# MB1297_STLINK_V2-1.net
KiCad netlist of a schematic drawn in Altium Designer
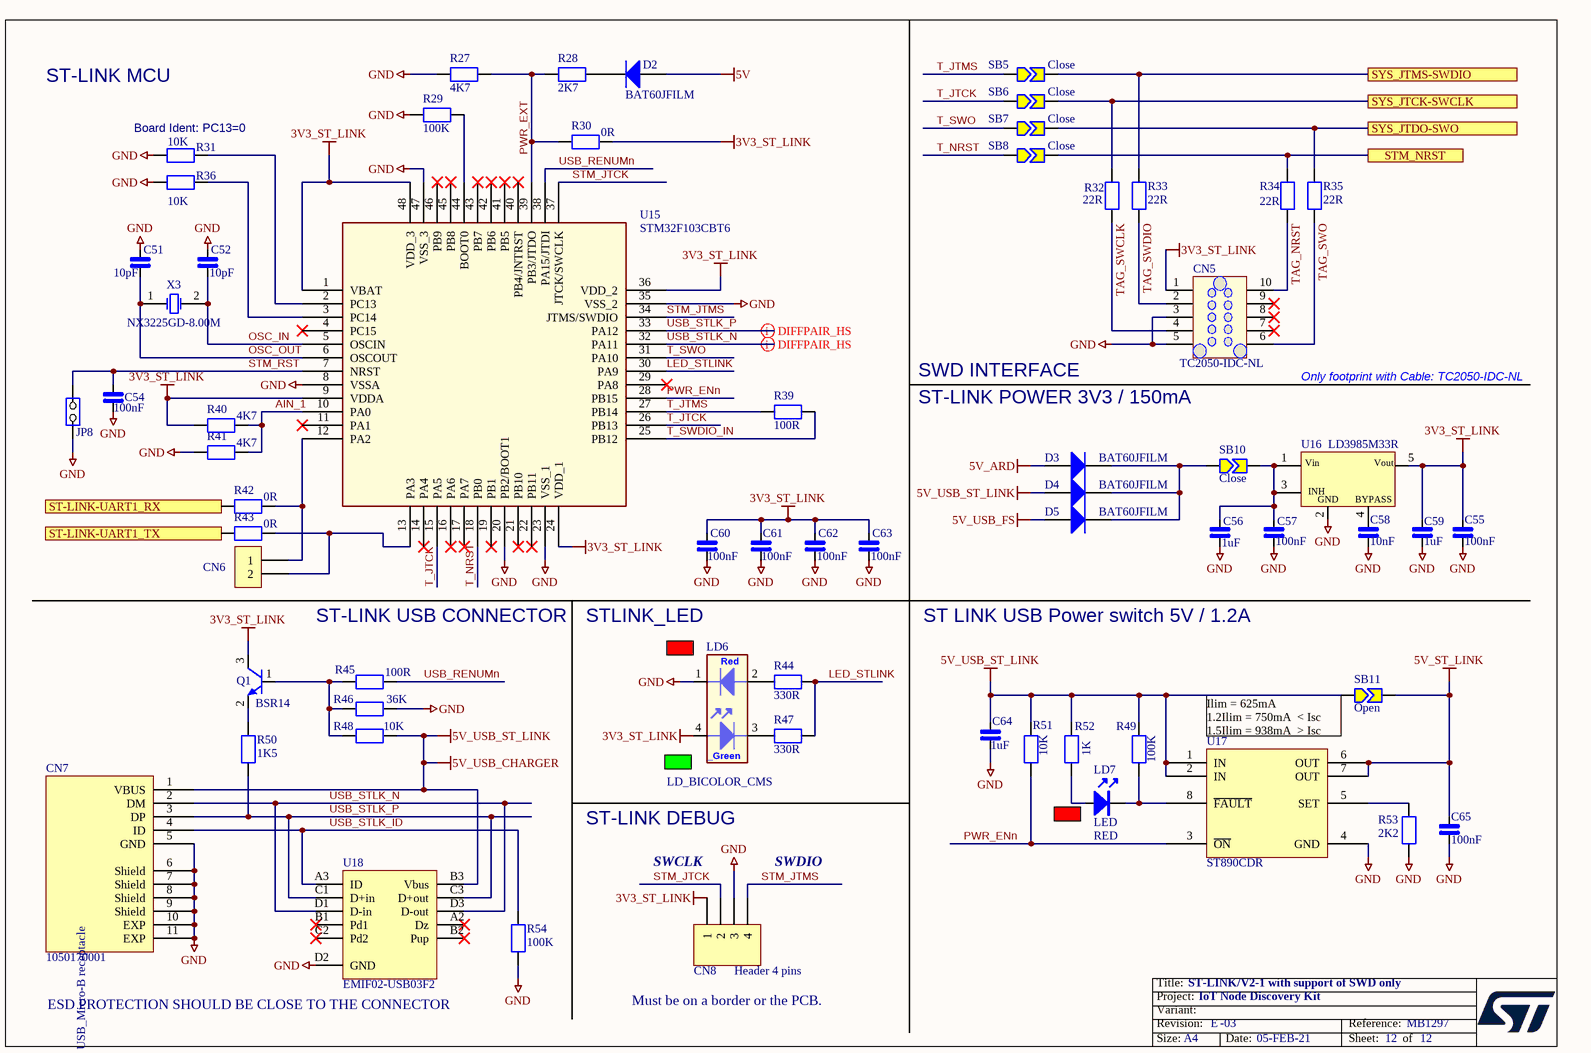
[diagram p0: MB1297_STLINK_V2-1.SCHDOC]

(export (version "E")
  (design (tool "Eeschema 10.0.6"))
  (components
    (comp (ref "C51")
      (value "10pF")
      (footprint "0402")
      (description "Capacitor_not polarized")
      (libsource (lib "ST_Lib3D") (part "CAP_NPOL"))
    )
    (comp (ref "C52")
      (value "10pF")
      (footprint "0402")
      (description "Capacitor_not polarized")
      (libsource (lib "ST_Lib3D") (part "CAP_NPOL"))
    )
    (comp (ref "C54")
      (value "100nF")
      (footprint "0402")
      (description "Capacitor_not polarized")
      (libsource (lib "ST_Lib3D") (part "CAP_NPOL"))
    )
    (comp (ref "C55")
      (value "100nF")
      (footprint "0402")
      (description "Capacitor_not polarized")
      (libsource (lib "ST_Lib3D") (part "CAP_NPOL"))
    )
    (comp (ref "C56")
      (value "1uF")
      (footprint "0402")
      (description "Capacitor_not polarized")
      (libsource (lib "ST_Lib3D") (part "CAP_NPOL"))
    )
    (comp (ref "C57")
      (value "100nF")
      (footprint "0402")
      (description "Capacitor_not polarized")
      (libsource (lib "ST_Lib3D") (part "CAP_NPOL"))
    )
    (comp (ref "C58")
      (value "10nF")
      (footprint "0402")
      (description "Capacitor_not polarized")
      (libsource (lib "ST_Lib3D") (part "CAP_NPOL"))
    )
    (comp (ref "C59")
      (value "1uF")
      (footprint "0402")
      (description "Capacitor_not polarized")
      (libsource (lib "ST_Lib3D") (part "CAP_NPOL"))
    )
    (comp (ref "C60")
      (value "100nF")
      (footprint "0402")
      (description "Capacitor_not polarized")
      (libsource (lib "ST_Lib3D") (part "CAP_NPOL"))
    )
    (comp (ref "C61")
      (value "100nF")
      (footprint "0402")
      (description "Capacitor_not polarized")
      (libsource (lib "ST_Lib3D") (part "CAP_NPOL"))
    )
    (comp (ref "C62")
      (value "100nF")
      (footprint "0402")
      (description "Capacitor_not polarized")
      (libsource (lib "ST_Lib3D") (part "CAP_NPOL"))
    )
    (comp (ref "C63")
      (value "100nF")
      (footprint "0402")
      (description "Capacitor_not polarized")
      (libsource (lib "ST_Lib3D") (part "CAP_NPOL"))
    )
    (comp (ref "C64")
      (value "1uF")
      (footprint "0402")
      (description "Capacitor_not polarized")
      (libsource (lib "ST_Lib3D") (part "CAP_NPOL"))
    )
    (comp (ref "C65")
      (value "100nF")
      (footprint "0402")
      (description "Capacitor_not polarized")
      (libsource (lib "ST_Lib3D") (part "CAP_NPOL"))
    )
    (comp (ref "CN5")
      (value "TC2050-IDC-NL")
      (footprint "CON_TAG-C_TC2050-IDC-NL")
      (description "Tag_Connector Header, 10-Pin, Dual row No legs")
      (libsource (lib "MCD_TEMP_PCH") (part "Tag-10-C"))
    )
    (comp (ref "CN6")
      (value "header 2 pins 2.54mm")
      (footprint "CON_SAMTEC_TSW-102-07-G-S")
      (description "Header 2 pins")
      (libsource (lib "MCD_TEMP_PCH") (part "Header 2 pins"))
    )
    (comp (ref "CN7")
      (value "1050170001")
      (footprint "CON_USBMICROB_MOLEX_105017-0001_H2P90")
      (description "USB-MICRO-B, 1050170001, SMT, MOLEX")
      (libsource (lib "MCD_TEMP_PCH") (part "1050170001"))
    )
    (comp (ref "CN8")
      (value "Header 4 pins")
      (footprint "CON_SAMTEC_TSW-104-07-G-S")
      (description "Header, 4-Pin")
      (libsource (lib "MCD_TEMP_PCH") (part "Header 4"))
    )
    (comp (ref "D2")
      (value "BAT60JFILM")
      (footprint "DIO_SOD323")
      (libsource (lib "MCD_TEMP_PCH") (part "BAT60JFILM"))
    )
    (comp (ref "D3")
      (value "BAT60JFILM")
      (footprint "DIO_SOD323")
      (libsource (lib "MCD_TEMP_PCH") (part "BAT60JFILM"))
    )
    (comp (ref "D4")
      (value "BAT60JFILM")
      (footprint "DIO_SOD323")
      (libsource (lib "MCD_TEMP_PCH") (part "BAT60JFILM"))
    )
    (comp (ref "D5")
      (value "BAT60JFILM")
      (footprint "DIO_SOD323")
      (libsource (lib "MCD_TEMP_PCH") (part "BAT60JFILM"))
    )
    (comp (ref "JP8")
      (value "Jumper_2.54mm")
      (footprint "CON_SAMTEC_TSW-102-07-G-S")
      (description "Connector jumper 1 position")
      (libsource (lib "MCD_TEMP_PCH") (part "TSW-102-07-x-S"))
    )
    (comp (ref "LD6")
      (value "LD_BICOLOR_CMS")
      (footprint "LED_BI-GR_HSMF-A201-A00J1")
      (description "Bicolor Led")
      (libsource (lib "MCD_TEMP_PCH") (part "LD_BICOLOR_CMS"))
    )
    (comp (ref "LD7")
      (value "LED")
      (footprint "0603_LED_RED")
      (description "Light-Emitting Diode")
      (fields (field (name "COLOR") "RED"))
      (libsource (lib "ST_Lib3D") (part "LED"))
    )
    (comp (ref "Q1")
      (value "BSR14")
      (footprint "ST_Lib3D:SOT23-3")
      (description "BSR14 NPN switching transistor SOT23 (Marking U8)")
      (libsource (lib "ST_Lib3D") (part "BSR14"))
    )
    (comp (ref "R27")
      (value "4K7")
      (footprint "0402")
      (description "Resistor")
      (libsource (lib "Lib3D_Altium10_Schlib") (part "RES"))
    )
    (comp (ref "R28")
      (value "2K7")
      (footprint "0402")
      (description "Resistor")
      (libsource (lib "Lib3D_Altium10_Schlib") (part "RES"))
    )
    (comp (ref "R29")
      (value "100K")
      (footprint "0402")
      (description "Resistor")
      (libsource (lib "Lib3D_Altium10_Schlib") (part "RES"))
    )
    (comp (ref "R30")
      (value "0R")
      (footprint "0402_RES")
      (description "Resistor")
      (libsource (lib "Lib3D_Altium10_Schlib") (part "RES"))
    )
    (comp (ref "R31")
      (value "10K")
      (footprint "0402")
      (description "Resistor")
      (libsource (lib "Lib3D_Altium10_Schlib") (part "RES"))
    )
    (comp (ref "R32")
      (value "22R")
      (footprint "0402")
      (description "Resistor")
      (libsource (lib "Lib3D_Altium10_Schlib") (part "RES"))
    )
    (comp (ref "R33")
      (value "22R")
      (footprint "0402")
      (description "Resistor")
      (libsource (lib "Lib3D_Altium10_Schlib") (part "RES"))
    )
    (comp (ref "R34")
      (value "22R")
      (footprint "0402")
      (description "Resistor")
      (libsource (lib "Lib3D_Altium10_Schlib") (part "RES"))
    )
    (comp (ref "R35")
      (value "22R")
      (footprint "0402")
      (description "Resistor")
      (libsource (lib "Lib3D_Altium10_Schlib") (part "RES"))
    )
    (comp (ref "R36")
      (value "10K")
      (footprint "0402")
      (description "Resistor")
      (libsource (lib "Lib3D_Altium10_Schlib") (part "RES"))
    )
    (comp (ref "R39")
      (value "100R")
      (footprint "0402")
      (description "Resistor")
      (libsource (lib "Lib3D_Altium10_Schlib") (part "RES"))
    )
    (comp (ref "R40")
      (value "4K7")
      (footprint "0402")
      (description "Resistor")
      (libsource (lib "Lib3D_Altium10_Schlib") (part "RES"))
    )
    (comp (ref "R41")
      (value "4K7")
      (footprint "0402")
      (description "Resistor")
      (libsource (lib "Lib3D_Altium10_Schlib") (part "RES"))
    )
    (comp (ref "R42")
      (value "0R")
      (footprint "0402_RES")
      (description "Resistor")
      (libsource (lib "Lib3D_Altium10_Schlib") (part "RES"))
    )
    (comp (ref "R43")
      (value "0R")
      (footprint "0402_RES")
      (description "Resistor")
      (libsource (lib "Lib3D_Altium10_Schlib") (part "RES"))
    )
    (comp (ref "R44")
      (value "330R")
      (footprint "0402")
      (description "Resistor")
      (libsource (lib "Lib3D_Altium10_Schlib") (part "RES"))
    )
    (comp (ref "R45")
      (value "100R")
      (footprint "0402")
      (description "Resistor")
      (libsource (lib "Lib3D_Altium10_Schlib") (part "RES"))
    )
    (comp (ref "R46")
      (value "36K")
      (footprint "0402")
      (description "Resistor")
      (libsource (lib "Lib3D_Altium10_Schlib") (part "RES"))
    )
    (comp (ref "R47")
      (value "330R")
      (footprint "0402")
      (description "Resistor")
      (libsource (lib "Lib3D_Altium10_Schlib") (part "RES"))
    )
    (comp (ref "R48")
      (value "10K")
      (footprint "0402")
      (description "Resistor")
      (libsource (lib "Lib3D_Altium10_Schlib") (part "RES"))
    )
    (comp (ref "R49")
      (value "100K")
      (footprint "0402_RES")
      (description "Resistor")
      (libsource (lib "Lib3D_Altium10_Schlib") (part "RES"))
    )
    (comp (ref "R50")
      (value "1K5")
      (footprint "0402_RES")
      (description "Resistor")
      (libsource (lib "Lib3D_Altium10_Schlib") (part "RES"))
    )
    (comp (ref "R51")
      (value "10K")
      (footprint "0402")
      (description "Resistor")
      (libsource (lib "Lib3D_Altium10_Schlib") (part "RES"))
    )
    (comp (ref "R52")
      (value "1K")
      (footprint "0402")
      (description "Resistor")
      (libsource (lib "Lib3D_Altium10_Schlib") (part "RES"))
    )
    (comp (ref "R53")
      (value "2K2")
      (footprint "0402")
      (description "Resistor")
      (libsource (lib "Lib3D_Altium10_Schlib") (part "RES"))
    )
    (comp (ref "R54")
      (value "100K")
      (footprint "0402")
      (description "Resistor")
      (libsource (lib "Lib3D_Altium10_Schlib") (part "RES"))
    )
    (comp (ref "SB5")
      (value "Close")
      (footprint "SB")
      (description "Solder Jumper")
      (fields (field (name "PUBLISHER") "Altium Limited"))
      (libsource (lib "Lib3D_Altium10_Schlib") (part "Strap2"))
    )
    (comp (ref "SB6")
      (value "Close")
      (footprint "SB")
      (description "Solder Jumper")
      (fields (field (name "PUBLISHER") "Altium Limited"))
      (libsource (lib "Lib3D_Altium10_Schlib") (part "Strap2"))
    )
    (comp (ref "SB7")
      (value "Close")
      (footprint "SB")
      (description "Solder Jumper")
      (fields (field (name "PUBLISHER") "Altium Limited"))
      (libsource (lib "Lib3D_Altium10_Schlib") (part "Strap2"))
    )
    (comp (ref "SB8")
      (value "Close")
      (footprint "SB")
      (description "Solder Jumper")
      (fields (field (name "PUBLISHER") "Altium Limited"))
      (libsource (lib "Lib3D_Altium10_Schlib") (part "Strap2"))
    )
    (comp (ref "SB10")
      (value "Close")
      (footprint "SB")
      (description "Solder Jumper")
      (fields (field (name "PUBLISHER") "Altium Limited"))
      (libsource (lib "Lib3D_Altium10_Schlib") (part "Strap2"))
    )
    (comp (ref "SB11")
      (value "Open")
      (footprint "SB")
      (description "Solder Jumper")
      (fields (field (name "PUBLISHER") "Altium Limited"))
      (libsource (lib "Lib3D_Altium10_Schlib") (part "Strap2"))
    )
    (comp (ref "U15")
      (value "STM32F103CBT6")
      (footprint "ICC_LQFP48_7X7_P050")
      (description "Medium-density performance line ARM-based 32-bit MCU with 128KB Flash")
      (libsource (lib "MCD_TEMP_PCH") (part "STM32F103CBT6"))
    )
    (comp (ref "U16")
      (value "LD3985M33R")
      (footprint "REG_SOT23-5L")
      (description "Ultra low drop-low noise BiCMOS voltage, regulators low ESR capacitors compatible")
      (libsource (lib "MCD_TEMP_PCH") (part "LD3985M33R"))
    )
    (comp (ref "U17")
      (value "ST890CDR")
      (footprint "ICC_SO8_5X4_P127")
      (description "1.2 A current limited high-side power switch with thermal shutdown")
      (libsource (lib "MCD_TEMP_PCH") (part "ST890CDR"))
    )
    (comp (ref "U18")
      (value "EMIF02-USB03F2")
      (footprint "ESD_FLIP-CHIP-BGA11_1P44X1P94_P050")
      (description "2-line IPAD, EMI filter including ESD protection")
      (libsource (lib "MCD_TEMP_PCH") (part "EMIF02-USB03F2"))
    )
    (comp (ref "X3")
      (value "NX3225GD-8.00M")
      (footprint "CRY_NX3225GD_2P")
      (description "Crystal 8Mhz, 8pF, -+50PPM, SMD")
      (libsource (lib "MCD_TEMP_PCH") (part "XTAL_8M_NX3225GD"))
    )
  )
  (nets
    (net (code "1") (name "/AIN_1") (class "Default")
      (node (ref "R40") (pin "1") (pinfunction "1_1") (pintype "passive"))
      (node (ref "R41") (pin "1") (pinfunction "1_1") (pintype "passive"))
      (node (ref "U15") (pin "10") (pinfunction "PA0_10") (pintype "passive"))
    )
    (net (code "2") (name "/LED_STLINK") (class "Default")
      (node (ref "R44") (pin "1") (pinfunction "1_1") (pintype "passive"))
      (node (ref "R47") (pin "1") (pinfunction "1_1") (pintype "passive"))
      (node (ref "U15") (pin "30") (pinfunction "PA9_30") (pintype "passive"))
    )
    (net (code "3") (name "/OSC_IN") (class "Default")
      (node (ref "C52") (pin "2") (pinfunction "2_2") (pintype "passive"))
      (node (ref "U15") (pin "5") (pinfunction "OSCIN_5") (pintype "passive"))
      (node (ref "X3") (pin "2") (pinfunction "OSC2_2") (pintype "passive"))
    )
    (net (code "4") (name "/OSC_OUT") (class "Default")
      (node (ref "C51") (pin "2") (pinfunction "2_2") (pintype "passive"))
      (node (ref "U15") (pin "6") (pinfunction "OSCOUT_6") (pintype "passive"))
      (node (ref "X3") (pin "1") (pinfunction "OSC1_1") (pintype "passive"))
    )
    (net (code "5") (name "/PWR_ENn") (class "Default")
      (node (ref "R51") (pin "1") (pinfunction "1_1") (pintype "passive"))
      (node (ref "U15") (pin "28") (pinfunction "PB15_28") (pintype "passive"))
      (node (ref "U17") (pin "3") (pinfunction "~{ON}_3") (pintype "passive"))
    )
    (net (code "6") (name "/PWR_EXT") (class "Default")
      (node (ref "R27") (pin "1") (pinfunction "1_1") (pintype "passive"))
      (node (ref "R28") (pin "2") (pinfunction "2_2") (pintype "passive"))
      (node (ref "R30") (pin "2") (pinfunction "2_2") (pintype "passive"))
      (node (ref "U15") (pin "39") (pinfunction "PB3/JTDO_39") (pintype "passive"))
    )
    (net (code "7") (name "/ST-LINK-UART1_RX") (class "Default")
      (node (ref "R42") (pin "2") (pinfunction "2_2") (pintype "passive"))
    )
    (net (code "8") (name "/ST-LINK-UART1_TX") (class "Default")
      (node (ref "R43") (pin "2") (pinfunction "2_2") (pintype "passive"))
    )
    (net (code "9") (name "/STM_JTCK") (class "Default")
      (node (ref "CN8") (pin "2") (pinfunction "2_2") (pintype "passive"))
      (node (ref "U15") (pin "37") (pinfunction "JTCK/SWCLK_37") (pintype "passive"))
    )
    (net (code "10") (name "/STM_JTMS") (class "Default")
      (node (ref "CN8") (pin "4") (pinfunction "4_4") (pintype "passive"))
      (node (ref "U15") (pin "34") (pinfunction "JTMS/SWDIO_34") (pintype "passive"))
    )
    (net (code "11") (name "/STM_NRST") (class "Default")
      (node (ref "R34") (pin "2") (pinfunction "2_2") (pintype "passive"))
      (node (ref "SB8") (pin "1") (pinfunction "1_1") (pintype "passive"))
    )
    (net (code "12") (name "/STM_RST") (class "Default")
      (node (ref "C54") (pin "1") (pinfunction "1_1") (pintype "passive"))
      (node (ref "JP8") (pin "2") (pinfunction "NO_2") (pintype "passive"))
      (node (ref "U15") (pin "7") (pinfunction "NRST_7") (pintype "passive"))
    )
    (net (code "13") (name "/SYS_JTCK-SWCLK") (class "Default")
      (node (ref "R32") (pin "2") (pinfunction "2_2") (pintype "passive"))
      (node (ref "SB6") (pin "1") (pinfunction "1_1") (pintype "passive"))
    )
    (net (code "14") (name "/SYS_JTDO-SWO") (class "Default")
      (node (ref "R35") (pin "2") (pinfunction "2_2") (pintype "passive"))
      (node (ref "SB7") (pin "1") (pinfunction "1_1") (pintype "passive"))
    )
    (net (code "15") (name "/SYS_JTMS-SWDIO") (class "Default")
      (node (ref "R33") (pin "2") (pinfunction "2_2") (pintype "passive"))
      (node (ref "SB5") (pin "1") (pinfunction "1_1") (pintype "passive"))
    )
    (net (code "16") (name "/TAG_NRST") (class "Default")
      (node (ref "CN5") (pin "10") (pinfunction "10_10") (pintype "passive"))
      (node (ref "R34") (pin "1") (pinfunction "1_1") (pintype "passive"))
    )
    (net (code "17") (name "/TAG_SWCLK") (class "Default")
      (node (ref "CN5") (pin "4") (pinfunction "4_4") (pintype "passive"))
      (node (ref "R32") (pin "1") (pinfunction "1_1") (pintype "passive"))
    )
    (net (code "18") (name "/TAG_SWDIO") (class "Default")
      (node (ref "CN5") (pin "2") (pinfunction "2_2") (pintype "passive"))
      (node (ref "R33") (pin "1") (pinfunction "1_1") (pintype "passive"))
    )
    (net (code "19") (name "/TAG_SWO") (class "Default")
      (node (ref "CN5") (pin "6") (pinfunction "6_6") (pintype "passive"))
      (node (ref "R35") (pin "1") (pinfunction "1_1") (pintype "passive"))
    )
    (net (code "20") (name "/T_JTCK") (class "Default")
      (node (ref "SB6") (pin "2") (pinfunction "2_2") (pintype "passive"))
      (node (ref "U15") (pin "15") (pinfunction "PA5_15") (pintype "passive"))
      (node (ref "U15") (pin "26") (pinfunction "PB13_26") (pintype "passive"))
    )
    (net (code "21") (name "/T_JTMS") (class "Default")
      (node (ref "R39") (pin "2") (pinfunction "2_2") (pintype "passive"))
      (node (ref "SB5") (pin "2") (pinfunction "2_2") (pintype "passive"))
      (node (ref "U15") (pin "27") (pinfunction "PB14_27") (pintype "passive"))
    )
    (net (code "22") (name "/T_NRST") (class "Default")
      (node (ref "SB8") (pin "2") (pinfunction "2_2") (pintype "passive"))
      (node (ref "U15") (pin "18") (pinfunction "PB0_18") (pintype "passive"))
    )
    (net (code "23") (name "/T_SWDIO_IN") (class "Default")
      (node (ref "R39") (pin "1") (pinfunction "1_1") (pintype "passive"))
      (node (ref "U15") (pin "25") (pinfunction "PB12_25") (pintype "passive"))
    )
    (net (code "24") (name "/T_SWO") (class "Default")
      (node (ref "SB7") (pin "2") (pinfunction "2_2") (pintype "passive"))
      (node (ref "U15") (pin "31") (pinfunction "PA10_31") (pintype "passive"))
    )
    (net (code "25") (name "/USB_RENUMn") (class "Default")
      (node (ref "R45") (pin "1") (pinfunction "1_1") (pintype "passive"))
      (node (ref "U15") (pin "38") (pinfunction "PA15/JTDI_38") (pintype "passive"))
    )
    (net (code "26") (name "/USB_STLK_ID") (class "Default")
      (node (ref "CN7") (pin "4") (pinfunction "ID_4") (pintype "passive"))
      (node (ref "R54") (pin "1") (pinfunction "1_1") (pintype "passive"))
      (node (ref "U18") (pin "A3") (pinfunction "ID_A3") (pintype "passive"))
    )
    (net (code "27") (name "/USB_STLK_N") (class "Default")
      (node (ref "CN7") (pin "2") (pinfunction "DM_2") (pintype "passive"))
      (node (ref "U15") (pin "32") (pinfunction "PA11_32") (pintype "passive"))
      (node (ref "U18") (pin "D1") (pinfunction "D-in_D1") (pintype "passive"))
      (node (ref "U18") (pin "D3") (pinfunction "D-out_D3") (pintype "passive"))
    )
    (net (code "28") (name "/USB_STLK_P") (class "Default")
      (node (ref "CN7") (pin "3") (pinfunction "DP_3") (pintype "passive"))
      (node (ref "R50") (pin "2") (pinfunction "2_2") (pintype "passive"))
      (node (ref "U15") (pin "33") (pinfunction "PA12_33") (pintype "passive"))
      (node (ref "U18") (pin "C1") (pinfunction "D+in_C1") (pintype "passive"))
      (node (ref "U18") (pin "C3") (pinfunction "D+out_C3") (pintype "passive"))
    )
    (net (code "29") (name "3V3_ST_LINK") (class "Default")
      (node (ref "C55") (pin "1") (pinfunction "1_1") (pintype "passive"))
      (node (ref "C59") (pin "1") (pinfunction "1_1") (pintype "passive"))
      (node (ref "C60") (pin "1") (pinfunction "1_1") (pintype "passive"))
      (node (ref "C61") (pin "1") (pinfunction "1_1") (pintype "passive"))
      (node (ref "C62") (pin "1") (pinfunction "1_1") (pintype "passive"))
      (node (ref "C63") (pin "1") (pinfunction "1_1") (pintype "passive"))
      (node (ref "CN5") (pin "1") (pinfunction "1_1") (pintype "passive"))
      (node (ref "CN8") (pin "1") (pinfunction "1_1") (pintype "passive"))
      (node (ref "LD6") (pin "4") (pinfunction "4_4") (pintype "passive"))
      (node (ref "Q1") (pin "3") (pinfunction "C_3") (pintype "passive"))
      (node (ref "R30") (pin "1") (pinfunction "1_1") (pintype "passive"))
      (node (ref "R40") (pin "2") (pinfunction "2_2") (pintype "passive"))
      (node (ref "U15") (pin "1") (pinfunction "VBAT_1") (pintype "passive"))
      (node (ref "U15") (pin "24") (pinfunction "VDD_1_24") (pintype "passive"))
      (node (ref "U15") (pin "36") (pinfunction "VDD_2_36") (pintype "passive"))
      (node (ref "U15") (pin "48") (pinfunction "VDD_3_48") (pintype "passive"))
      (node (ref "U15") (pin "9") (pinfunction "VDDA_9") (pintype "passive"))
      (node (ref "U16") (pin "5") (pinfunction "Vout_5") (pintype "passive"))
    )
    (net (code "30") (name "5V") (class "Default")
      (node (ref "D2") (pin "1") (pinfunction "A_1") (pintype "passive"))
    )
    (net (code "31") (name "5V_ARD") (class "Default")
      (node (ref "D3") (pin "1") (pinfunction "A_1") (pintype "passive"))
    )
    (net (code "32") (name "5V_ST_LINK") (class "Default")
      (node (ref "C65") (pin "1") (pinfunction "1_1") (pintype "passive"))
      (node (ref "SB11") (pin "1") (pinfunction "1_1") (pintype "passive"))
      (node (ref "U17") (pin "6") (pinfunction "OUT_6") (pintype "passive"))
      (node (ref "U17") (pin "7") (pinfunction "OUT_7") (pintype "passive"))
    )
    (net (code "33") (name "5V_USB_CHARGER") (class "Default")
      (node (ref "C64") (pin "1") (pinfunction "1_1") (pintype "passive"))
      (node (ref "CN7") (pin "1") (pinfunction "VBUS_1") (pintype "passive"))
      (node (ref "D4") (pin "1") (pinfunction "A_1") (pintype "passive"))
      (node (ref "R48") (pin "1") (pinfunction "1_1") (pintype "passive"))
      (node (ref "R49") (pin "2") (pinfunction "2_2") (pintype "passive"))
      (node (ref "R51") (pin "2") (pinfunction "2_2") (pintype "passive"))
      (node (ref "R52") (pin "2") (pinfunction "2_2") (pintype "passive"))
      (node (ref "SB11") (pin "2") (pinfunction "2_2") (pintype "passive"))
      (node (ref "U17") (pin "1") (pinfunction "IN_1") (pintype "passive"))
      (node (ref "U17") (pin "2") (pinfunction "IN_2") (pintype "passive"))
      (node (ref "U18") (pin "B3") (pinfunction "Vbus_B3") (pintype "passive"))
    )
    (net (code "34") (name "5V_USB_FS") (class "Default")
      (node (ref "D5") (pin "1") (pinfunction "A_1") (pintype "passive"))
    )
    (net (code "35") (name "GND") (class "Default")
      (node (ref "C51") (pin "1") (pinfunction "1_1") (pintype "passive"))
      (node (ref "C52") (pin "1") (pinfunction "1_1") (pintype "passive"))
      (node (ref "C54") (pin "2") (pinfunction "2_2") (pintype "passive"))
      (node (ref "C55") (pin "2") (pinfunction "2_2") (pintype "passive"))
      (node (ref "C56") (pin "2") (pinfunction "2_2") (pintype "passive"))
      (node (ref "C57") (pin "2") (pinfunction "2_2") (pintype "passive"))
      (node (ref "C58") (pin "2") (pinfunction "2_2") (pintype "passive"))
      (node (ref "C59") (pin "2") (pinfunction "2_2") (pintype "passive"))
      (node (ref "C60") (pin "2") (pinfunction "2_2") (pintype "passive"))
      (node (ref "C61") (pin "2") (pinfunction "2_2") (pintype "passive"))
      (node (ref "C62") (pin "2") (pinfunction "2_2") (pintype "passive"))
      (node (ref "C63") (pin "2") (pinfunction "2_2") (pintype "passive"))
      (node (ref "C64") (pin "2") (pinfunction "2_2") (pintype "passive"))
      (node (ref "C65") (pin "2") (pinfunction "2_2") (pintype "passive"))
      (node (ref "CN5") (pin "3") (pinfunction "3_3") (pintype "passive"))
      (node (ref "CN5") (pin "5") (pinfunction "5_5") (pintype "passive"))
      (node (ref "CN7") (pin "10") (pinfunction "EXP_10") (pintype "passive"))
      (node (ref "CN7") (pin "11") (pinfunction "EXP_11") (pintype "passive"))
      (node (ref "CN7") (pin "5") (pinfunction "GND_5") (pintype "passive"))
      (node (ref "CN7") (pin "6") (pinfunction "Shield_6") (pintype "passive"))
      (node (ref "CN7") (pin "7") (pinfunction "Shield_7") (pintype "passive"))
      (node (ref "CN7") (pin "8") (pinfunction "Shield_8") (pintype "passive"))
      (node (ref "CN7") (pin "9") (pinfunction "Shield_9") (pintype "passive"))
      (node (ref "CN8") (pin "3") (pinfunction "3_3") (pintype "passive"))
      (node (ref "JP8") (pin "1") (pinfunction "COMMON_1") (pintype "passive"))
      (node (ref "LD6") (pin "1") (pinfunction "1_1") (pintype "passive"))
      (node (ref "R27") (pin "2") (pinfunction "2_2") (pintype "passive"))
      (node (ref "R29") (pin "2") (pinfunction "2_2") (pintype "passive"))
      (node (ref "R31") (pin "2") (pinfunction "2_2") (pintype "passive"))
      (node (ref "R36") (pin "2") (pinfunction "2_2") (pintype "passive"))
      (node (ref "R41") (pin "2") (pinfunction "2_2") (pintype "passive"))
      (node (ref "R46") (pin "1") (pinfunction "1_1") (pintype "passive"))
      (node (ref "R53") (pin "1") (pinfunction "1_1") (pintype "passive"))
      (node (ref "R54") (pin "2") (pinfunction "2_2") (pintype "passive"))
      (node (ref "U15") (pin "20") (pinfunction "PB2/BOOT1_20") (pintype "passive"))
      (node (ref "U15") (pin "23") (pinfunction "VSS_1_23") (pintype "passive"))
      (node (ref "U15") (pin "35") (pinfunction "VSS_2_35") (pintype "passive"))
      (node (ref "U15") (pin "47") (pinfunction "VSS_3_47") (pintype "passive"))
      (node (ref "U15") (pin "8") (pinfunction "VSSA_8") (pintype "passive"))
      (node (ref "U16") (pin "2") (pinfunction "GND_2") (pintype "passive"))
      (node (ref "U17") (pin "4") (pinfunction "GND_4") (pintype "passive"))
      (node (ref "U18") (pin "D2") (pinfunction "GND_D2") (pintype "passive"))
    )
    (net (code "36") (name "Net-(D2-K)") (class "Default")
      (node (ref "D2") (pin "2") (pinfunction "K_2") (pintype "passive"))
      (node (ref "R28") (pin "1") (pinfunction "1_1") (pintype "passive"))
    )
    (net (code "37") (name "Net-(D3-K)") (class "Default")
      (node (ref "D3") (pin "2") (pinfunction "K_2") (pintype "passive"))
      (node (ref "D4") (pin "2") (pinfunction "K_2") (pintype "passive"))
      (node (ref "D5") (pin "2") (pinfunction "K_2") (pintype "passive"))
      (node (ref "SB10") (pin "2") (pinfunction "2_2") (pintype "passive"))
    )
    (net (code "38") (name "Net-(LD6-Pad2)") (class "Default")
      (node (ref "LD6") (pin "2") (pinfunction "2_2") (pintype "passive"))
      (node (ref "R44") (pin "2") (pinfunction "2_2") (pintype "passive"))
    )
    (net (code "39") (name "Net-(LD6-Pad3)") (class "Default")
      (node (ref "LD6") (pin "3") (pinfunction "3_3") (pintype "passive"))
      (node (ref "R47") (pin "2") (pinfunction "2_2") (pintype "passive"))
    )
    (net (code "40") (name "Net-(LD7-PadA)") (class "Default")
      (node (ref "LD7") (pin "A") (pinfunction "A_A") (pintype "passive"))
      (node (ref "R52") (pin "1") (pinfunction "1_1") (pintype "passive"))
    )
    (net (code "41") (name "Net-(Q1-B)") (class "Default")
      (node (ref "Q1") (pin "1") (pinfunction "B_1") (pintype "passive"))
      (node (ref "R45") (pin "2") (pinfunction "2_2") (pintype "passive"))
      (node (ref "R46") (pin "2") (pinfunction "2_2") (pintype "passive"))
      (node (ref "R48") (pin "2") (pinfunction "2_2") (pintype "passive"))
    )
    (net (code "42") (name "Net-(Q1-E)") (class "Default")
      (node (ref "Q1") (pin "2") (pinfunction "E_2") (pintype "passive"))
      (node (ref "R50") (pin "1") (pinfunction "1_1") (pintype "passive"))
    )
    (net (code "43") (name "Net-(U15-BOOT0)") (class "Default")
      (node (ref "R29") (pin "1") (pinfunction "1_1") (pintype "passive"))
      (node (ref "U15") (pin "44") (pinfunction "BOOT0_44") (pintype "passive"))
    )
    (net (code "44") (name "Net-(U15-PA2)") (class "Default")
      (node (ref "CN6") (pin "1") (pinfunction "1_1") (pintype "passive"))
      (node (ref "R42") (pin "1") (pinfunction "1_1") (pintype "passive"))
      (node (ref "U15") (pin "12") (pinfunction "PA2_12") (pintype "passive"))
    )
    (net (code "45") (name "Net-(U15-PA3)") (class "Default")
      (node (ref "CN6") (pin "2") (pinfunction "2_2") (pintype "passive"))
      (node (ref "R43") (pin "1") (pinfunction "1_1") (pintype "passive"))
      (node (ref "U15") (pin "13") (pinfunction "PA3_13") (pintype "passive"))
    )
    (net (code "46") (name "Net-(U15-PC13)") (class "Default")
      (node (ref "R31") (pin "1") (pinfunction "1_1") (pintype "passive"))
      (node (ref "U15") (pin "2") (pinfunction "PC13_2") (pintype "passive"))
    )
    (net (code "47") (name "Net-(U15-PC14)") (class "Default")
      (node (ref "R36") (pin "1") (pinfunction "1_1") (pintype "passive"))
      (node (ref "U15") (pin "3") (pinfunction "PC14_3") (pintype "passive"))
    )
    (net (code "48") (name "Net-(U16-BYPASS)") (class "Default")
      (node (ref "C58") (pin "1") (pinfunction "1_1") (pintype "passive"))
      (node (ref "U16") (pin "4") (pinfunction "BYPASS_4") (pintype "passive"))
    )
    (net (code "49") (name "Net-(U16-CE)") (class "Default")
      (node (ref "C56") (pin "1") (pinfunction "1_1") (pintype "passive"))
      (node (ref "C57") (pin "1") (pinfunction "1_1") (pintype "passive"))
      (node (ref "SB10") (pin "1") (pinfunction "1_1") (pintype "passive"))
      (node (ref "U16") (pin "1") (pinfunction "Vin_1") (pintype "passive"))
      (node (ref "U16") (pin "3") (pinfunction "CE_3") (pintype "passive"))
    )
    (net (code "50") (name "Net-(U17-SET)") (class "Default")
      (node (ref "R53") (pin "2") (pinfunction "2_2") (pintype "passive"))
      (node (ref "U17") (pin "5") (pinfunction "SET_5") (pintype "passive"))
    )
    (net (code "51") (name "Net-(U17-~{FAULT})") (class "Default")
      (node (ref "LD7") (pin "K") (pinfunction "K_K") (pintype "passive"))
      (node (ref "R49") (pin "1") (pinfunction "1_1") (pintype "passive"))
      (node (ref "U17") (pin "8") (pinfunction "~{FAULT}_8") (pintype "passive"))
    )
    (net (code "52") (name "unconnected-(CN5-Pad7)") (class "Default")
      (node (ref "CN5") (pin "7") (pinfunction "7_7") (pintype "passive+no_connect"))
    )
    (net (code "53") (name "unconnected-(CN5-Pad8)") (class "Default")
      (node (ref "CN5") (pin "8") (pinfunction "8_8") (pintype "passive+no_connect"))
    )
    (net (code "54") (name "unconnected-(CN5-Pad9)") (class "Default")
      (node (ref "CN5") (pin "9") (pinfunction "9_9") (pintype "passive+no_connect"))
    )
    (net (code "55") (name "unconnected-(U15-PA1-Pad11)") (class "Default")
      (node (ref "U15") (pin "11") (pinfunction "PA1_11") (pintype "passive+no_connect"))
    )
    (net (code "56") (name "unconnected-(U15-PA4-Pad14)") (class "Default")
      (node (ref "U15") (pin "14") (pinfunction "PA4_14") (pintype "passive+no_connect"))
    )
    (net (code "57") (name "unconnected-(U15-PA6-Pad16)") (class "Default")
      (node (ref "U15") (pin "16") (pinfunction "PA6_16") (pintype "passive+no_connect"))
    )
    (net (code "58") (name "unconnected-(U15-PA7-Pad17)") (class "Default")
      (node (ref "U15") (pin "17") (pinfunction "PA7_17") (pintype "passive+no_connect"))
    )
    (net (code "59") (name "unconnected-(U15-PA8-Pad29)") (class "Default")
      (node (ref "U15") (pin "29") (pinfunction "PA8_29") (pintype "passive+no_connect"))
    )
    (net (code "60") (name "unconnected-(U15-PB1-Pad19)") (class "Default")
      (node (ref "U15") (pin "19") (pinfunction "PB1_19") (pintype "passive+no_connect"))
    )
    (net (code "61") (name "unconnected-(U15-PB4{slash}JNTRST-Pad40)") (class "Default")
      (node (ref "U15") (pin "40") (pinfunction "PB4/JNTRST_40") (pintype "passive+no_connect"))
    )
    (net (code "62") (name "unconnected-(U15-PB5-Pad41)") (class "Default")
      (node (ref "U15") (pin "41") (pinfunction "PB5_41") (pintype "passive+no_connect"))
    )
    (net (code "63") (name "unconnected-(U15-PB6-Pad42)") (class "Default")
      (node (ref "U15") (pin "42") (pinfunction "PB6_42") (pintype "passive+no_connect"))
    )
    (net (code "64") (name "unconnected-(U15-PB7-Pad43)") (class "Default")
      (node (ref "U15") (pin "43") (pinfunction "PB7_43") (pintype "passive+no_connect"))
    )
    (net (code "65") (name "unconnected-(U15-PB8-Pad45)") (class "Default")
      (node (ref "U15") (pin "45") (pinfunction "PB8_45") (pintype "passive+no_connect"))
    )
    (net (code "66") (name "unconnected-(U15-PB9-Pad46)") (class "Default")
      (node (ref "U15") (pin "46") (pinfunction "PB9_46") (pintype "passive+no_connect"))
    )
    (net (code "67") (name "unconnected-(U15-PB10-Pad21)") (class "Default")
      (node (ref "U15") (pin "21") (pinfunction "PB10_21") (pintype "passive+no_connect"))
    )
    (net (code "68") (name "unconnected-(U15-PB11-Pad22)") (class "Default")
      (node (ref "U15") (pin "22") (pinfunction "PB11_22") (pintype "passive+no_connect"))
    )
    (net (code "69") (name "unconnected-(U15-PC15-Pad4)") (class "Default")
      (node (ref "U15") (pin "4") (pinfunction "PC15_4") (pintype "passive+no_connect"))
    )
    (net (code "70") (name "unconnected-(U18-Dz-PadA2)") (class "Default")
      (node (ref "U18") (pin "A2") (pinfunction "Dz_A2") (pintype "passive+no_connect"))
    )
    (net (code "71") (name "unconnected-(U18-Pd1-PadB1)") (class "Default")
      (node (ref "U18") (pin "B1") (pinfunction "Pd1_B1") (pintype "passive+no_connect"))
    )
    (net (code "72") (name "unconnected-(U18-Pd2-PadC2)") (class "Default")
      (node (ref "U18") (pin "C2") (pinfunction "Pd2_C2") (pintype "passive+no_connect"))
    )
    (net (code "73") (name "unconnected-(U18-Pup-PadB2)") (class "Default")
      (node (ref "U18") (pin "B2") (pinfunction "Pup_B2") (pintype "passive+no_connect"))
    )
  )
)
